# Sheet1.net
KiCad netlist of a schematic drawn in Altium Designer
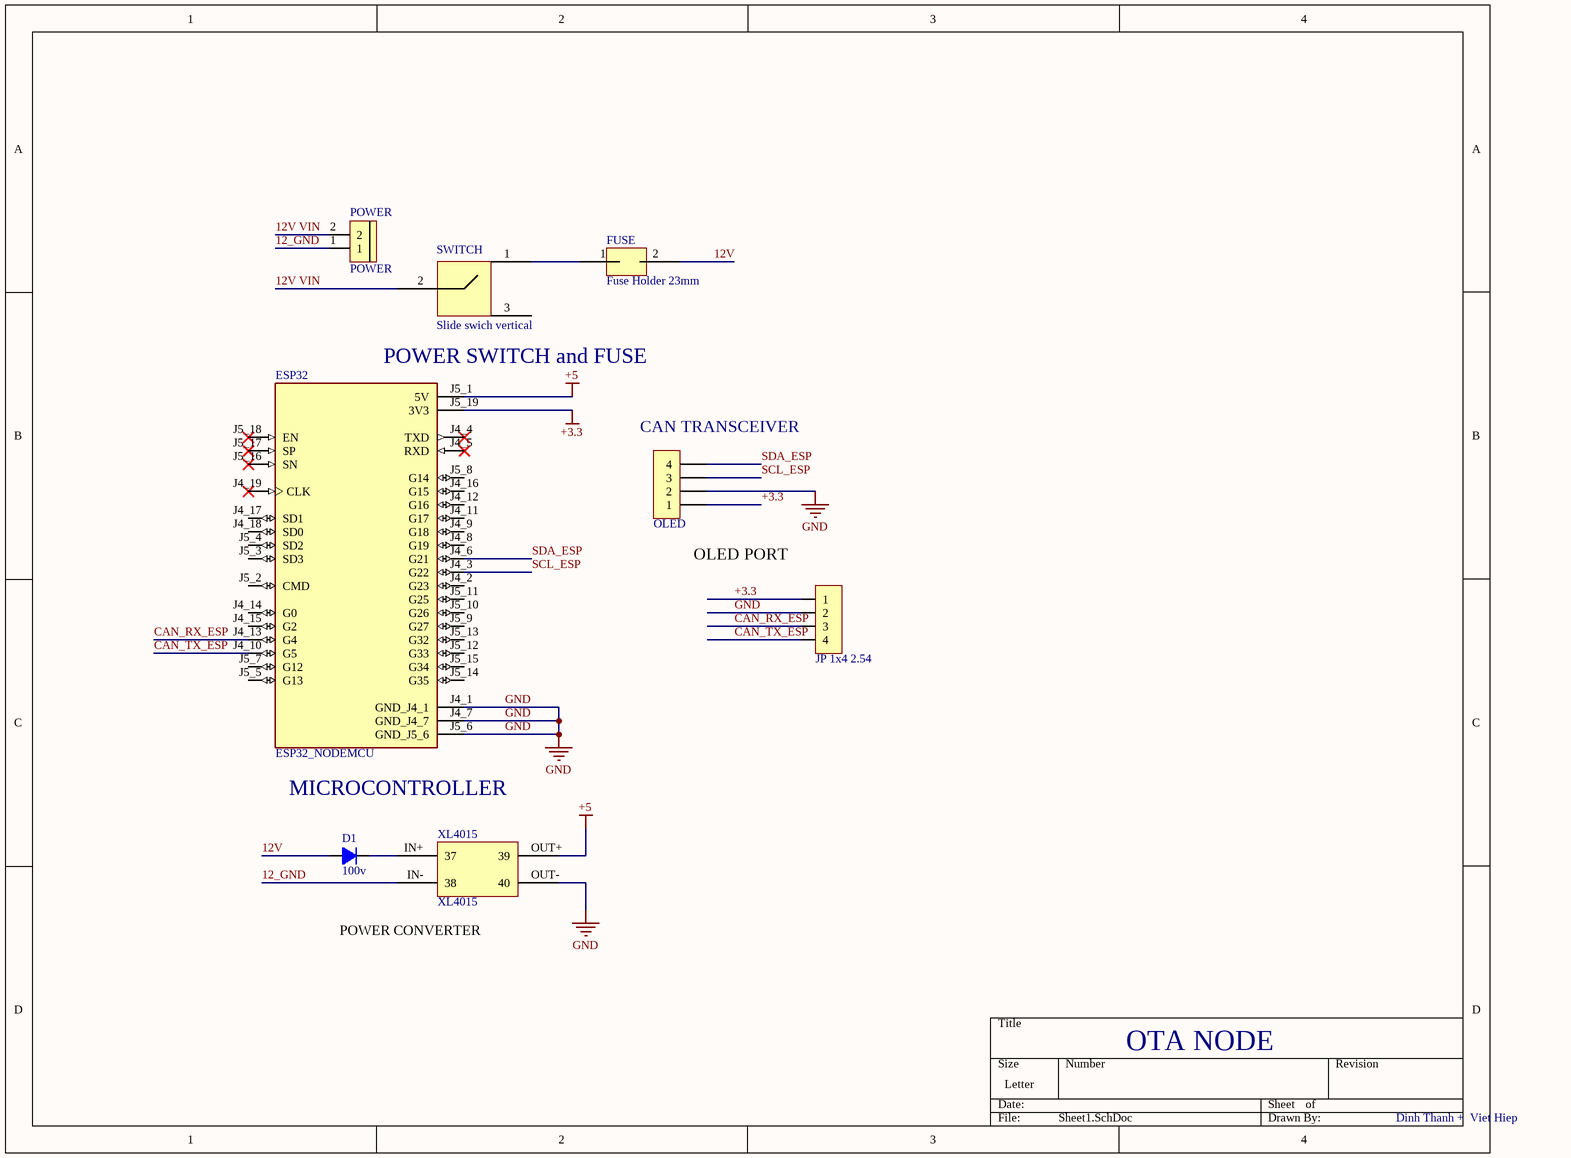
[diagram p0: Sheet1.SchDoc]

(export (version "E")
  (design (tool "Eeschema 10.0.6"))
  (components
    (comp (ref "CAN")
      (value "JP 1x4 2.54")
      (footprint "JP 1x4 CC")
      (description "Cắm")
      (libsource (lib "Jump") (part "JP 1x4 2.54 Cai Cong"))
    )
    (comp (ref "D1")
      (value "100v")
      (footprint "DIODE 1A")
      (description "Cắm")
      (libsource (lib "DIODE") (part "Diode 1N4007"))
    )
    (comp (ref "ESP32")
      (value "ESP32_NODEMCU")
      (footprint "ESP32 SMALL")
      (fields (field (name "MF") "Espressif Systems") (field (name "MP") "ESP32 NODEMCU"))
      (libsource (lib "ESP32_NODEMCU") (part "ESP32_NODEMCU"))
    )
    (comp (ref "FUSE")
      (value "Fuse Holder 23mm")
      (footprint "Fuse3")
      (libsource (lib "Fuse") (part "Fuse Holder 23mm"))
    )
    (comp (ref "OLED")
      (value "OLED")
      (footprint "XH2.54M-4")
      (description "Cắm")
      (libsource (lib "Header") (part "Header 4P 2.54 Duc Thang"))
    )
    (comp (ref "POWER")
      (value "POWER")
      (footprint "Con 2 KF301 5.08")
      (description "Cắm")
      (libsource (lib "Connector") (part "CON 2 KF301"))
    )
    (comp (ref "SWITCH")
      (value "Slide swich vertical")
      (footprint "SW102T")
      (libsource (lib "BUTTON-SWITCH") (part "Slide swich vertical"))
    )
    (comp (ref "XL4015") (value "XL4015") (footprint "XL4015") (libsource (lib "XL4015") (part "XL4015")))
  )
  (nets
    (net (code "1") (name "+3.3") (class "Default")
      (node (ref "CAN") (pin "1") (pinfunction "1_1") (pintype "passive"))
      (node (ref "ESP32") (pin "J5_19") (pinfunction "3V3_J5_19") (pintype "power_in"))
      (node (ref "OLED") (pin "1") (pinfunction "1_1") (pintype "passive"))
    )
    (net (code "2") (name "+5") (class "Default")
      (node (ref "ESP32") (pin "J5_1") (pinfunction "5V_J5_1") (pintype "power_in"))
      (node (ref "XL4015") (pin "OUT+") (pinfunction "39_OUT+") (pintype "passive"))
    )
    (net (code "3") (name "/12V") (class "Default")
      (node (ref "D1") (pin "1") (pinfunction "A_1") (pintype "passive"))
      (node (ref "FUSE") (pin "2") (pinfunction "46_2") (pintype "passive"))
    )
    (net (code "4") (name "/12V VIN") (class "Default")
      (node (ref "POWER") (pin "2") (pinfunction "2_2") (pintype "passive"))
      (node (ref "SWITCH") (pin "2") (pinfunction "41_2") (pintype "passive"))
    )
    (net (code "5") (name "/12_GND") (class "Default")
      (node (ref "POWER") (pin "1") (pinfunction "1_1") (pintype "passive"))
      (node (ref "XL4015") (pin "IN-") (pinfunction "38_IN-") (pintype "passive"))
    )
    (net (code "6") (name "/CAN_RX_ESP") (class "Default")
      (node (ref "CAN") (pin "3") (pinfunction "3_3") (pintype "passive"))
      (node (ref "ESP32") (pin "J4_13") (pinfunction "G4_J4_13") (pintype "bidirectional"))
    )
    (net (code "7") (name "/CAN_TX_ESP") (class "Default")
      (node (ref "CAN") (pin "4") (pinfunction "4_4") (pintype "passive"))
      (node (ref "ESP32") (pin "J4_10") (pinfunction "G5_J4_10") (pintype "bidirectional"))
    )
    (net (code "8") (name "/SCL_ESP") (class "Default")
      (node (ref "ESP32") (pin "J4_3") (pinfunction "G22_J4_3") (pintype "bidirectional"))
      (node (ref "OLED") (pin "3") (pinfunction "3_3") (pintype "passive"))
    )
    (net (code "9") (name "/SDA_ESP") (class "Default")
      (node (ref "ESP32") (pin "J4_6") (pinfunction "G21_J4_6") (pintype "bidirectional"))
      (node (ref "OLED") (pin "4") (pinfunction "4_4") (pintype "passive"))
    )
    (net (code "10") (name "GND") (class "Default")
      (node (ref "CAN") (pin "2") (pinfunction "2_2") (pintype "passive"))
      (node (ref "ESP32") (pin "J4_1") (pinfunction "GND_J4_1_J4_1") (pintype "power_in"))
      (node (ref "ESP32") (pin "J4_7") (pinfunction "GND_J4_7_J4_7") (pintype "power_in"))
      (node (ref "ESP32") (pin "J5_6") (pinfunction "GND_J5_6_J5_6") (pintype "power_in"))
      (node (ref "OLED") (pin "2") (pinfunction "2_2") (pintype "passive"))
      (node (ref "XL4015") (pin "OUT-") (pinfunction "40_OUT-") (pintype "passive"))
    )
    (net (code "11") (name "Net-(D1-K)") (class "Default")
      (node (ref "D1") (pin "2") (pinfunction "K_2") (pintype "passive"))
      (node (ref "XL4015") (pin "IN+") (pinfunction "37_IN+") (pintype "passive"))
    )
    (net (code "12") (name "Net-(FUSE-45)") (class "Default")
      (node (ref "FUSE") (pin "1") (pinfunction "45_1") (pintype "passive"))
      (node (ref "SWITCH") (pin "1") (pinfunction "42_1") (pintype "passive"))
    )
    (net (code "13") (name "unconnected-(ESP32-CLK-PadJ4_19)") (class "Default")
      (node (ref "ESP32") (pin "J4_19") (pinfunction "CLK_J4_19") (pintype "input+no_connect"))
    )
    (net (code "14") (name "unconnected-(ESP32-CMD-PadJ5_2)") (class "Default")
      (node (ref "ESP32") (pin "J5_2") (pinfunction "CMD_J5_2") (pintype "bidirectional"))
    )
    (net (code "15") (name "unconnected-(ESP32-EN-PadJ5_18)") (class "Default")
      (node (ref "ESP32") (pin "J5_18") (pinfunction "EN_J5_18") (pintype "input+no_connect"))
    )
    (net (code "16") (name "unconnected-(ESP32-G0-PadJ4_14)") (class "Default")
      (node (ref "ESP32") (pin "J4_14") (pinfunction "G0_J4_14") (pintype "bidirectional"))
    )
    (net (code "17") (name "unconnected-(ESP32-G2-PadJ4_15)") (class "Default")
      (node (ref "ESP32") (pin "J4_15") (pinfunction "G2_J4_15") (pintype "bidirectional"))
    )
    (net (code "18") (name "unconnected-(ESP32-G12-PadJ5_7)") (class "Default")
      (node (ref "ESP32") (pin "J5_7") (pinfunction "G12_J5_7") (pintype "bidirectional"))
    )
    (net (code "19") (name "unconnected-(ESP32-G13-PadJ5_5)") (class "Default")
      (node (ref "ESP32") (pin "J5_5") (pinfunction "G13_J5_5") (pintype "bidirectional"))
    )
    (net (code "20") (name "unconnected-(ESP32-G14-PadJ5_8)") (class "Default")
      (node (ref "ESP32") (pin "J5_8") (pinfunction "G14_J5_8") (pintype "bidirectional"))
    )
    (net (code "21") (name "unconnected-(ESP32-G15-PadJ4_16)") (class "Default")
      (node (ref "ESP32") (pin "J4_16") (pinfunction "G15_J4_16") (pintype "bidirectional"))
    )
    (net (code "22") (name "unconnected-(ESP32-G16-PadJ4_12)") (class "Default")
      (node (ref "ESP32") (pin "J4_12") (pinfunction "G16_J4_12") (pintype "bidirectional"))
    )
    (net (code "23") (name "unconnected-(ESP32-G17-PadJ4_11)") (class "Default")
      (node (ref "ESP32") (pin "J4_11") (pinfunction "G17_J4_11") (pintype "bidirectional"))
    )
    (net (code "24") (name "unconnected-(ESP32-G18-PadJ4_9)") (class "Default")
      (node (ref "ESP32") (pin "J4_9") (pinfunction "G18_J4_9") (pintype "bidirectional"))
    )
    (net (code "25") (name "unconnected-(ESP32-G19-PadJ4_8)") (class "Default")
      (node (ref "ESP32") (pin "J4_8") (pinfunction "G19_J4_8") (pintype "bidirectional"))
    )
    (net (code "26") (name "unconnected-(ESP32-G23-PadJ4_2)") (class "Default")
      (node (ref "ESP32") (pin "J4_2") (pinfunction "G23_J4_2") (pintype "bidirectional"))
    )
    (net (code "27") (name "unconnected-(ESP32-G25-PadJ5_11)") (class "Default")
      (node (ref "ESP32") (pin "J5_11") (pinfunction "G25_J5_11") (pintype "bidirectional"))
    )
    (net (code "28") (name "unconnected-(ESP32-G26-PadJ5_10)") (class "Default")
      (node (ref "ESP32") (pin "J5_10") (pinfunction "G26_J5_10") (pintype "bidirectional"))
    )
    (net (code "29") (name "unconnected-(ESP32-G27-PadJ5_9)") (class "Default")
      (node (ref "ESP32") (pin "J5_9") (pinfunction "G27_J5_9") (pintype "bidirectional"))
    )
    (net (code "30") (name "unconnected-(ESP32-G32-PadJ5_13)") (class "Default")
      (node (ref "ESP32") (pin "J5_13") (pinfunction "G32_J5_13") (pintype "bidirectional"))
    )
    (net (code "31") (name "unconnected-(ESP32-G33-PadJ5_12)") (class "Default")
      (node (ref "ESP32") (pin "J5_12") (pinfunction "G33_J5_12") (pintype "bidirectional"))
    )
    (net (code "32") (name "unconnected-(ESP32-G34-PadJ5_15)") (class "Default")
      (node (ref "ESP32") (pin "J5_15") (pinfunction "G34_J5_15") (pintype "bidirectional"))
    )
    (net (code "33") (name "unconnected-(ESP32-G35-PadJ5_14)") (class "Default")
      (node (ref "ESP32") (pin "J5_14") (pinfunction "G35_J5_14") (pintype "bidirectional"))
    )
    (net (code "34") (name "unconnected-(ESP32-RXD-PadJ4_5)") (class "Default")
      (node (ref "ESP32") (pin "J4_5") (pinfunction "RXD_J4_5") (pintype "input+no_connect"))
    )
    (net (code "35") (name "unconnected-(ESP32-SD0-PadJ4_18)") (class "Default")
      (node (ref "ESP32") (pin "J4_18") (pinfunction "SD0_J4_18") (pintype "bidirectional"))
    )
    (net (code "36") (name "unconnected-(ESP32-SD1-PadJ4_17)") (class "Default")
      (node (ref "ESP32") (pin "J4_17") (pinfunction "SD1_J4_17") (pintype "bidirectional"))
    )
    (net (code "37") (name "unconnected-(ESP32-SD2-PadJ5_4)") (class "Default")
      (node (ref "ESP32") (pin "J5_4") (pinfunction "SD2_J5_4") (pintype "bidirectional"))
    )
    (net (code "38") (name "unconnected-(ESP32-SD3-PadJ5_3)") (class "Default")
      (node (ref "ESP32") (pin "J5_3") (pinfunction "SD3_J5_3") (pintype "bidirectional"))
    )
    (net (code "39") (name "unconnected-(ESP32-SN-PadJ5_16)") (class "Default")
      (node (ref "ESP32") (pin "J5_16") (pinfunction "SN_J5_16") (pintype "input+no_connect"))
    )
    (net (code "40") (name "unconnected-(ESP32-SP-PadJ5_17)") (class "Default")
      (node (ref "ESP32") (pin "J5_17") (pinfunction "SP_J5_17") (pintype "input+no_connect"))
    )
    (net (code "41") (name "unconnected-(ESP32-TXD-PadJ4_4)") (class "Default")
      (node (ref "ESP32") (pin "J4_4") (pinfunction "TXD_J4_4") (pintype "output+no_connect"))
    )
    (net (code "42") (name "unconnected-(SWITCH-43-Pad3)") (class "Default")
      (node (ref "SWITCH") (pin "3") (pinfunction "43_3") (pintype "passive"))
    )
  )
)
